# Radio_Board.net
KiCad netlist of a schematic drawn in EAGLE
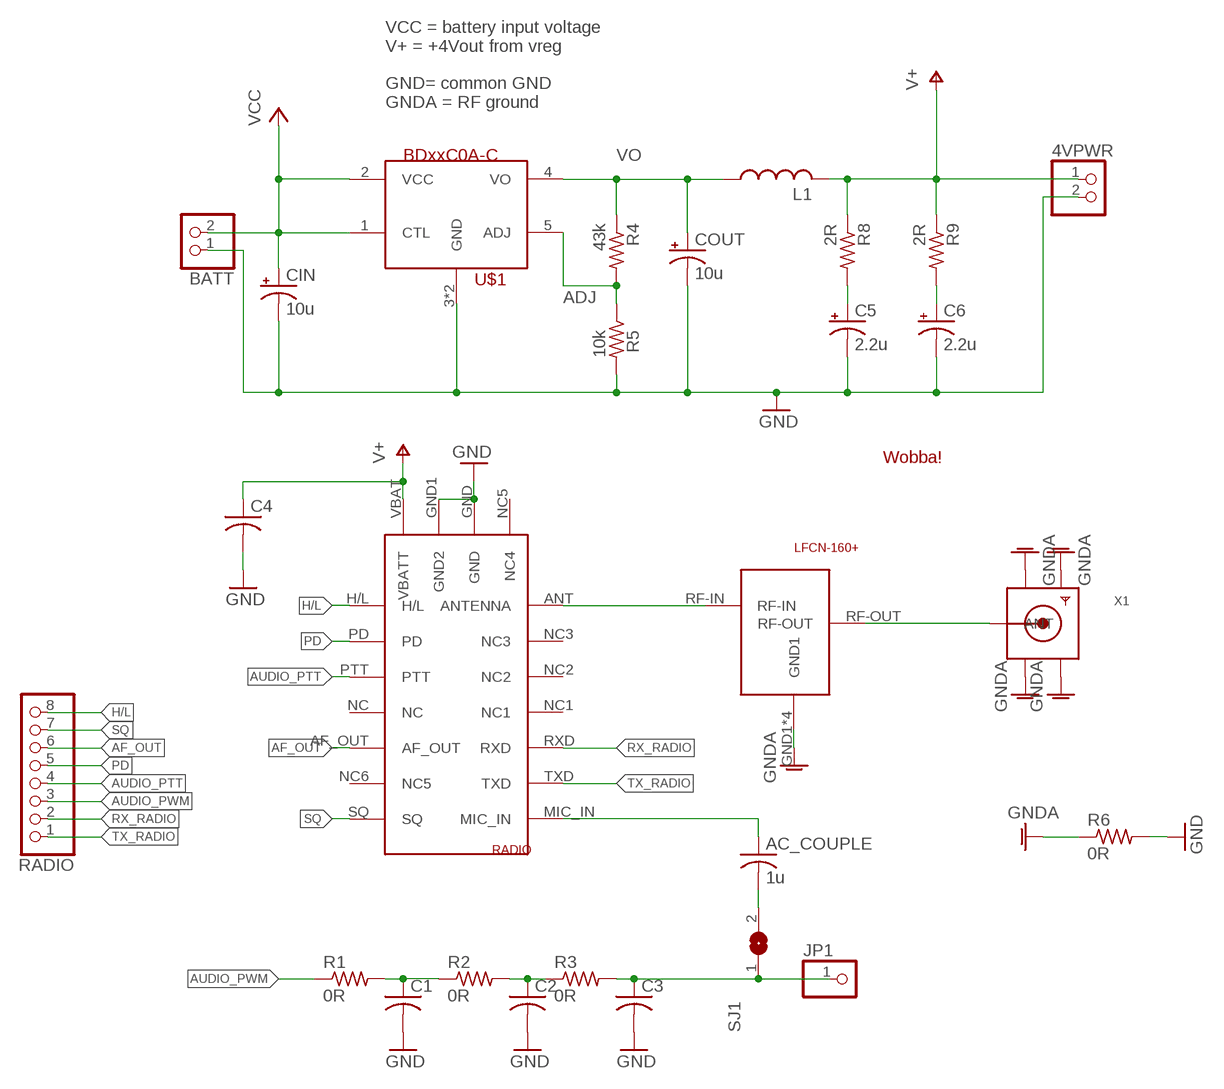
[diagram p0: schematic, sheet 1]

(export (version "E")
  (design (tool "Eeschema 10.0.6"))
  (components
    (comp (ref "4VPWR")
      (value "PINHD-1X2")
      (footprint "eagle-import:1X02")
      (libsource (lib "eagle-import") (part "PINHD-1X2"))
    )
    (comp (ref "AC_COUPLE")
      (value "1u")
      (footprint "eagle-import:C0805")
      (libsource (lib "eagle-import") (part "C-USC0805"))
    )
    (comp (ref "BATT")
      (value "PINHD-1X2")
      (footprint "eagle-import:1X02")
      (libsource (lib "eagle-import") (part "PINHD-1X2"))
    )
    (comp (ref "C1")
      (value "C-USC0805")
      (footprint "eagle-import:C0805")
      (libsource (lib "eagle-import") (part "C-USC0805"))
    )
    (comp (ref "C2")
      (value "C-USC0805")
      (footprint "eagle-import:C0805")
      (libsource (lib "eagle-import") (part "C-USC0805"))
    )
    (comp (ref "C3")
      (value "C-USC0805")
      (footprint "eagle-import:C0805")
      (libsource (lib "eagle-import") (part "C-USC0805"))
    )
    (comp (ref "C4")
      (value "100n")
      (footprint "eagle-import:C0805")
      (libsource (lib "eagle-import") (part "C-USC0805"))
    )
    (comp (ref "C5")
      (value "2.2u")
      (footprint "eagle-import:PANASONIC_A")
      (libsource (lib "eagle-import") (part "CPOL-USA"))
    )
    (comp (ref "C6")
      (value "2.2u")
      (footprint "eagle-import:PANASONIC_A")
      (libsource (lib "eagle-import") (part "CPOL-USA"))
    )
    (comp (ref "CIN")
      (value "10u")
      (footprint "eagle-import:PANASONIC_A")
      (libsource (lib "eagle-import") (part "CPOL-USA"))
    )
    (comp (ref "COUT")
      (value "10u")
      (footprint "eagle-import:PANASONIC_A")
      (libsource (lib "eagle-import") (part "CPOL-USA"))
    )
    (comp (ref "JP1")
      (value "PINHD-1X1")
      (footprint "eagle-import:1X01")
      (libsource (lib "eagle-import") (part "PINHD-1X1"))
    )
    (comp (ref "L1")
      (value "L-USL3225M")
      (footprint "eagle-import:L3225M")
      (libsource (lib "eagle-import") (part "L-USL3225M"))
    )
    (comp (ref "R1")
      (value "0R")
      (footprint "eagle-import:R0805")
      (libsource (lib "eagle-import") (part "R-US_R0805"))
    )
    (comp (ref "R2")
      (value "0R")
      (footprint "eagle-import:R0805")
      (libsource (lib "eagle-import") (part "R-US_R0805"))
    )
    (comp (ref "R3")
      (value "0R")
      (footprint "eagle-import:R0805")
      (libsource (lib "eagle-import") (part "R-US_R0805"))
    )
    (comp (ref "R4")
      (value "43k")
      (footprint "eagle-import:R0805")
      (libsource (lib "eagle-import") (part "R-US_R0805"))
    )
    (comp (ref "R5")
      (value "10k")
      (footprint "eagle-import:R0805")
      (libsource (lib "eagle-import") (part "R-US_R0805"))
    )
    (comp (ref "R6")
      (value "0R")
      (footprint "eagle-import:R0805")
      (libsource (lib "eagle-import") (part "R-US_R0805"))
    )
    (comp (ref "R8")
      (value "2R")
      (footprint "eagle-import:R0805")
      (libsource (lib "eagle-import") (part "R-US_R0805"))
    )
    (comp (ref "R9")
      (value "2R")
      (footprint "eagle-import:R0805")
      (libsource (lib "eagle-import") (part "R-US_R0805"))
    )
    (comp (ref "RADIO")
      (value "PINHD-1X8")
      (footprint "eagle-import:1X08")
      (libsource (lib "eagle-import") (part "PINHD-1X8"))
    )
    (comp (ref "SJ1") (value "SJ") (footprint "eagle-import:SJ") (libsource (lib "eagle-import") (part "SJ")))
    (comp (ref "U$1")
      (value "BDXXC0A-CBD00C0AWHFP-CTR")
      (footprint "eagle-import:HRP5")
      (libsource (lib "eagle-import") (part "BDXXC0A-CBD00C0AWHFP-CTR"))
    )
    (comp (ref "U$2")
      (value "WOBBUFFET")
      (footprint "eagle-import:WOBBUFFET")
      (libsource (lib "eagle-import") (part "WOBBUFFET"))
    )
    (comp (ref "U$4")
      (value "RADIO")
      (footprint "eagle-import:RADIO")
      (libsource (lib "eagle-import") (part "RADIO"))
    )
    (comp (ref "U$6")
      (value "LFCN-160+")
      (footprint "eagle-import:LFCN-160+")
      (libsource (lib "eagle-import") (part "LFCN-160+"))
    )
    (comp (ref "X1")
      (value "SMACONNECTOR_EDGE")
      (footprint "eagle-import:SMA_EDGELAUNCH")
      (libsource (lib "eagle-import") (part "SMACONNECTOR_EDGE"))
    )
  )
  (nets
    (net (code "1") (name "/ADJ") (class "Default")
      (node (ref "R4") (pin "2") (pinfunction "2_2") (pintype "passive"))
      (node (ref "R5") (pin "1") (pinfunction "1_1") (pintype "passive"))
      (node (ref "U$1") (pin "5") (pinfunction "ADJ_5") (pintype "bidirectional"))
    )
    (net (code "2") (name "/VO") (class "Default")
      (node (ref "COUT") (pin "+") (pinfunction "+_+") (pintype "passive"))
      (node (ref "L1") (pin "1") (pinfunction "1_1") (pintype "passive"))
      (node (ref "R4") (pin "1") (pinfunction "1_1") (pintype "passive"))
      (node (ref "U$1") (pin "4") (pinfunction "VO_4") (pintype "power_in"))
    )
    (net (code "3") (name "AF_OUT") (class "Default")
      (node (ref "RADIO") (pin "6") (pinfunction "6_6") (pintype "passive"))
      (node (ref "U$4") (pin "AF_OUT") (pinfunction "AF_OUT_AF_OUT") (pintype "bidirectional"))
    )
    (net (code "4") (name "AUDIO_PTT") (class "Default")
      (node (ref "RADIO") (pin "4") (pinfunction "4_4") (pintype "passive"))
      (node (ref "U$4") (pin "PTT") (pinfunction "PTT_PTT") (pintype "bidirectional"))
    )
    (net (code "5") (name "AUDIO_PWM") (class "Default")
      (node (ref "R1") (pin "1") (pinfunction "1_1") (pintype "passive"))
      (node (ref "RADIO") (pin "3") (pinfunction "3_3") (pintype "passive"))
    )
    (net (code "6") (name "GND") (class "Default")
      (node (ref "4VPWR") (pin "2") (pinfunction "2_2") (pintype "passive"))
      (node (ref "BATT") (pin "1") (pinfunction "1_1") (pintype "passive"))
      (node (ref "C1") (pin "2") (pinfunction "2_2") (pintype "passive"))
      (node (ref "C2") (pin "2") (pinfunction "2_2") (pintype "passive"))
      (node (ref "C3") (pin "2") (pinfunction "2_2") (pintype "passive"))
      (node (ref "C4") (pin "2") (pinfunction "2_2") (pintype "passive"))
      (node (ref "C5") (pin "-") (pinfunction "-_-") (pintype "passive"))
      (node (ref "C6") (pin "-") (pinfunction "-_-") (pintype "passive"))
      (node (ref "CIN") (pin "-") (pinfunction "-_-") (pintype "passive"))
      (node (ref "COUT") (pin "-") (pinfunction "-_-") (pintype "passive"))
      (node (ref "R5") (pin "2") (pinfunction "2_2") (pintype "passive"))
      (node (ref "R6") (pin "2") (pinfunction "2_2") (pintype "passive"))
      (node (ref "U$1") (pin "3") (pinfunction "GND_3") (pintype "bidirectional"))
      (node (ref "U$1") (pin "6") (pinfunction "GND_6") (pintype "bidirectional"))
      (node (ref "U$4") (pin "GND") (pinfunction "GND_GND") (pintype "bidirectional"))
      (node (ref "U$4") (pin "GND1") (pinfunction "GND2_GND1") (pintype "bidirectional"))
    )
    (net (code "7") (name "GNDA") (class "Default")
      (node (ref "R6") (pin "1") (pinfunction "1_1") (pintype "passive"))
      (node (ref "U$6") (pin "GND1") (pinfunction "GND1_GND1") (pintype "power_in"))
      (node (ref "U$6") (pin "GND2") (pinfunction "GND1_GND2") (pintype "power_in"))
      (node (ref "U$6") (pin "P$1") (pinfunction "GND1_P$1") (pintype "power_in"))
      (node (ref "U$6") (pin "P$2") (pinfunction "GND1_P$2") (pintype "power_in"))
      (node (ref "X1") (pin "GND@1") (pinfunction "GND4_GND@1") (pintype "power_in"))
      (node (ref "X1") (pin "GND@2") (pinfunction "GND3_GND@2") (pintype "power_in"))
      (node (ref "X1") (pin "GND@3") (pinfunction "GND2_GND@3") (pintype "power_in"))
      (node (ref "X1") (pin "GND@4") (pinfunction "GND1_GND@4") (pintype "power_in"))
    )
    (net (code "8") (name "H{slash}L") (class "Default")
      (node (ref "RADIO") (pin "8") (pinfunction "8_8") (pintype "passive"))
      (node (ref "U$4") (pin "H/L") (pinfunction "H/L_H/L") (pintype "bidirectional"))
    )
    (net (code "9") (name "Net-(AC_COUPLE-Pad1)") (class "Default")
      (node (ref "AC_COUPLE") (pin "1") (pinfunction "1_1") (pintype "passive"))
      (node (ref "U$4") (pin "MIC_IN") (pinfunction "MIC_IN_MIC_IN") (pintype "bidirectional"))
    )
    (net (code "10") (name "Net-(AC_COUPLE-Pad2)") (class "Default")
      (node (ref "AC_COUPLE") (pin "2") (pinfunction "2_2") (pintype "passive"))
      (node (ref "SJ1") (pin "2") (pinfunction "2_2") (pintype "passive"))
    )
    (net (code "11") (name "Net-(C1-Pad1)") (class "Default")
      (node (ref "C1") (pin "1") (pinfunction "1_1") (pintype "passive"))
      (node (ref "R1") (pin "2") (pinfunction "2_2") (pintype "passive"))
      (node (ref "R2") (pin "1") (pinfunction "1_1") (pintype "passive"))
    )
    (net (code "12") (name "Net-(C2-Pad1)") (class "Default")
      (node (ref "C2") (pin "1") (pinfunction "1_1") (pintype "passive"))
      (node (ref "R2") (pin "2") (pinfunction "2_2") (pintype "passive"))
      (node (ref "R3") (pin "1") (pinfunction "1_1") (pintype "passive"))
    )
    (net (code "13") (name "Net-(C3-Pad1)") (class "Default")
      (node (ref "C3") (pin "1") (pinfunction "1_1") (pintype "passive"))
      (node (ref "JP1") (pin "1") (pinfunction "1_1") (pintype "passive"))
      (node (ref "R3") (pin "2") (pinfunction "2_2") (pintype "passive"))
      (node (ref "SJ1") (pin "1") (pinfunction "1_1") (pintype "passive"))
    )
    (net (code "14") (name "Net-(C5-Pad+)") (class "Default")
      (node (ref "C5") (pin "+") (pinfunction "+_+") (pintype "passive"))
      (node (ref "R8") (pin "2") (pinfunction "2_2") (pintype "passive"))
    )
    (net (code "15") (name "Net-(C6-Pad+)") (class "Default")
      (node (ref "C6") (pin "+") (pinfunction "+_+") (pintype "passive"))
      (node (ref "R9") (pin "2") (pinfunction "2_2") (pintype "passive"))
    )
    (net (code "16") (name "Net-(U$4-ANTENNA)") (class "Default")
      (node (ref "U$4") (pin "ANT") (pinfunction "ANTENNA_ANT") (pintype "bidirectional"))
      (node (ref "U$6") (pin "RF-IN") (pinfunction "RF-IN_RF-IN") (pintype "bidirectional"))
    )
    (net (code "17") (name "Net-(X1-ANT)") (class "Default")
      (node (ref "U$6") (pin "RF-OUT") (pinfunction "RF-OUT_RF-OUT") (pintype "bidirectional"))
      (node (ref "X1") (pin "P") (pinfunction "ANT_P") (pintype "bidirectional"))
    )
    (net (code "18") (name "PD") (class "Default")
      (node (ref "RADIO") (pin "5") (pinfunction "5_5") (pintype "passive"))
      (node (ref "U$4") (pin "PD") (pinfunction "PD_PD") (pintype "bidirectional"))
    )
    (net (code "19") (name "RX_RADIO") (class "Default")
      (node (ref "RADIO") (pin "2") (pinfunction "2_2") (pintype "passive"))
      (node (ref "U$4") (pin "RXD") (pinfunction "RXD_RXD") (pintype "bidirectional"))
    )
    (net (code "20") (name "SQ") (class "Default")
      (node (ref "RADIO") (pin "7") (pinfunction "7_7") (pintype "passive"))
      (node (ref "U$4") (pin "SQ") (pinfunction "SQ_SQ") (pintype "bidirectional"))
    )
    (net (code "21") (name "TX_RADIO") (class "Default")
      (node (ref "RADIO") (pin "1") (pinfunction "1_1") (pintype "passive"))
      (node (ref "U$4") (pin "TXD") (pinfunction "TXD_TXD") (pintype "bidirectional"))
    )
    (net (code "22") (name "V+") (class "Default")
      (node (ref "4VPWR") (pin "1") (pinfunction "1_1") (pintype "passive"))
      (node (ref "C4") (pin "1") (pinfunction "1_1") (pintype "passive"))
      (node (ref "L1") (pin "2") (pinfunction "2_2") (pintype "passive"))
      (node (ref "R8") (pin "1") (pinfunction "1_1") (pintype "passive"))
      (node (ref "R9") (pin "1") (pinfunction "1_1") (pintype "passive"))
      (node (ref "U$4") (pin "VBAT") (pinfunction "VBATT_VBAT") (pintype "bidirectional"))
    )
    (net (code "23") (name "VCC") (class "Default")
      (node (ref "BATT") (pin "2") (pinfunction "2_2") (pintype "passive"))
      (node (ref "CIN") (pin "+") (pinfunction "+_+") (pintype "passive"))
      (node (ref "U$1") (pin "1") (pinfunction "CTL_1") (pintype "bidirectional"))
      (node (ref "U$1") (pin "2") (pinfunction "VCC_2") (pintype "power_in"))
    )
    (net (code "24") (name "unconnected-(U$4-NC4-PadNC5)") (class "Default")
      (node (ref "U$4") (pin "NC5") (pinfunction "NC4_NC5") (pintype "bidirectional"))
    )
    (net (code "25") (name "unconnected-(U$4-NC5-PadNC6)") (class "Default")
      (node (ref "U$4") (pin "NC6") (pinfunction "NC5_NC6") (pintype "bidirectional"))
    )
    (net (code "26") (name "unconnected-(U$4-PadNC)") (class "Default")
      (node (ref "U$4") (pin "NC") (pinfunction "NC_NC") (pintype "bidirectional"))
    )
    (net (code "27") (name "unconnected-(U$4-PadNC1)") (class "Default")
      (node (ref "U$4") (pin "NC1") (pinfunction "NC1_NC1") (pintype "bidirectional"))
    )
    (net (code "28") (name "unconnected-(U$4-PadNC2)") (class "Default")
      (node (ref "U$4") (pin "NC2") (pinfunction "NC2_NC2") (pintype "bidirectional"))
    )
    (net (code "29") (name "unconnected-(U$4-PadNC3)") (class "Default")
      (node (ref "U$4") (pin "NC3") (pinfunction "NC3_NC3") (pintype "bidirectional"))
    )
  )
)
